# Power_Input.net
KiCad netlist of a schematic drawn in Altium Designer
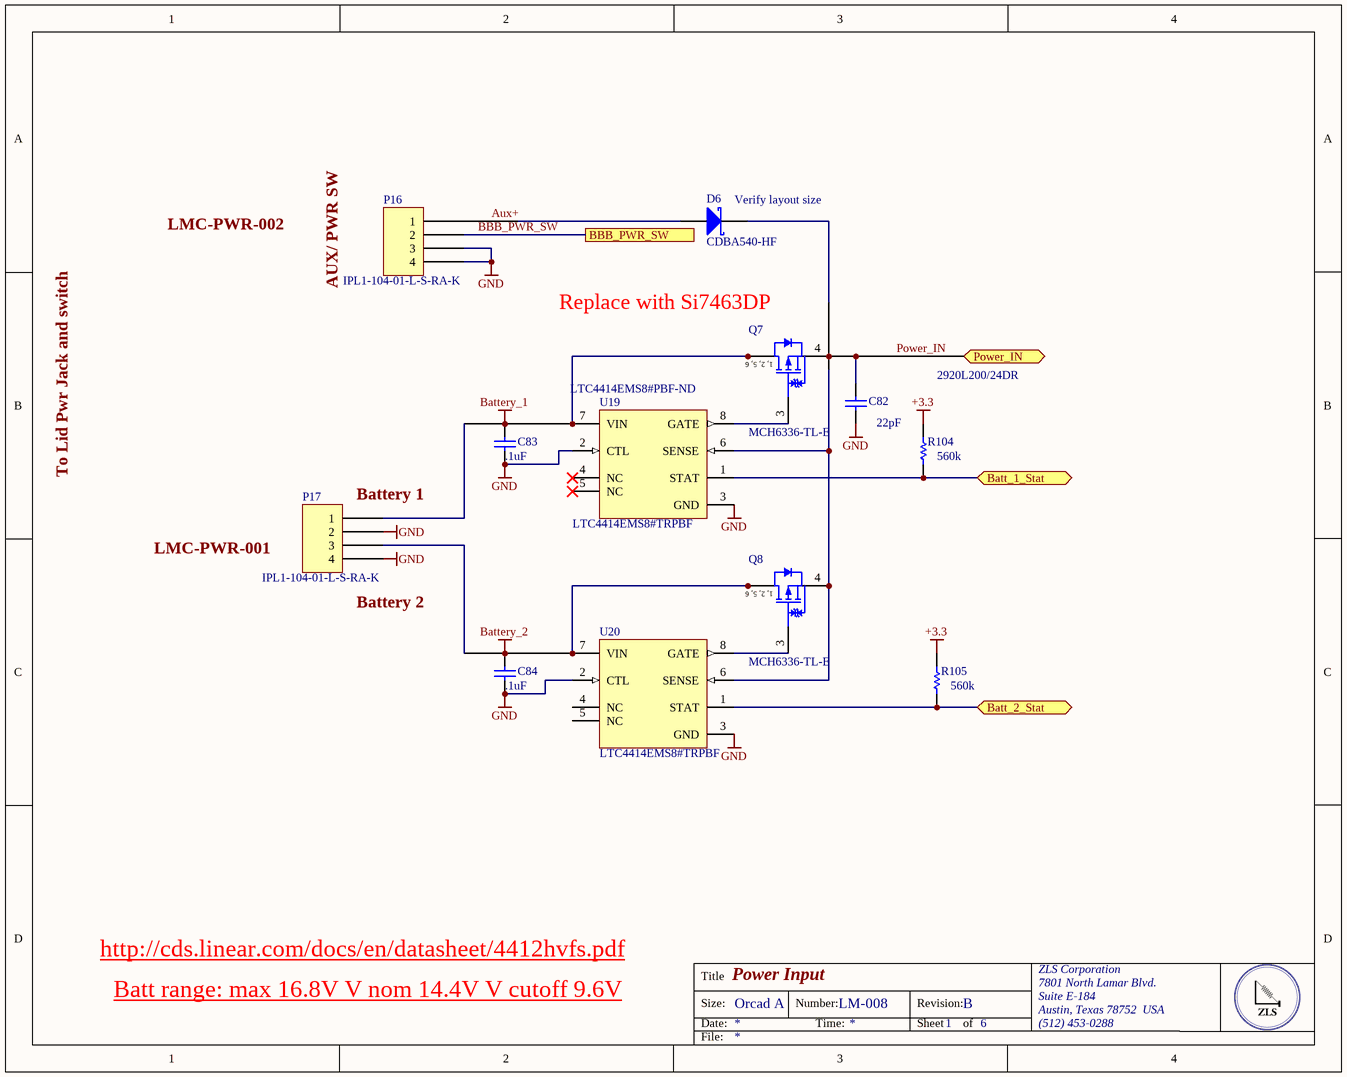
[diagram p0: Power_Input.SchDoc]

(export (version "E")
  (design (tool "Eeschema 10.0.6"))
  (components
    (comp (ref "C82")
      (value "CAP CER 10UF 6.3V X5R 1206")
      (footprint "CAPC1206(3216)130_N")
      (fields
        (field (name "MANUFACTURER") "Taiyo Yuden")
        (field (name "MANUFACTURER PART NUMBER") "JMK316BJ106ML-T")
        (field (name "TOLERANCE") "±20%")
        (field (name "CAPACITANCE") "22pF")
      )
      (libsource (lib "Altium Content Vault") (part "CMP-1037-04913-1"))
    )
    (comp (ref "C83")
      (value "CAP CER 10UF 6.3V X5R 1206")
      (footprint "CAPC1206(3216)130_N")
      (fields
        (field (name "MANUFACTURER") "Taiyo Yuden")
        (field (name "MANUFACTURER PART NUMBER") "JMK316BJ106ML-T")
        (field (name "TOLERANCE") "±20%")
        (field (name "CAPACITANCE") ".1uF")
      )
      (libsource (lib "Altium Content Vault") (part "CMP-1037-04913-1"))
    )
    (comp (ref "C84")
      (value "CAP CER 10UF 6.3V X5R 1206")
      (footprint "CAPC1206(3216)130_N")
      (fields
        (field (name "MANUFACTURER") "Taiyo Yuden")
        (field (name "MANUFACTURER PART NUMBER") "JMK316BJ106ML-T")
        (field (name "TOLERANCE") "±20%")
        (field (name "CAPACITANCE") ".1uF")
      )
      (libsource (lib "Altium Content Vault") (part "CMP-1037-04913-1"))
    )
    (comp (ref "D6")
      (value "CDBA540-HF")
      (footprint "VISH-DO-214AC-2_M")
      (description "DIODE SCHOTTKY 40V 5A DO214AB")
      (fields (field (name "MANUFACTURER") "Comchip Technology"))
      (libsource (lib "Miscellaneous Devices") (part "D Schottky"))
    )
    (comp (ref "P16")
      (value "IPL1-104-01-L-S-RA-K")
      (footprint "IPL1-104-01-L-S-RA-K")
      (fields
        (field (name "MANUFACTURER") "Samtec Inc.")
        (field (name "MANUFACTURER PART NUMBER") "IPL1-104-01-L-S-RA-K")
      )
      (libsource (lib "ZLS_Schematic_lib") (part "IPL1-104-01-L-S-RA-K"))
    )
    (comp (ref "P17")
      (value "IPL1-104-01-L-S-RA-K")
      (footprint "IPL1-104-01-L-S-RA-K")
      (fields
        (field (name "MANUFACTURER") "Samtec Inc.")
        (field (name "MANUFACTURER PART NUMBER") "IPL1-104-01-L-S-RA-K")
      )
      (libsource (lib "ZLS_Schematic_lib") (part "IPL1-104-01-L-S-RA-K"))
    )
    (comp (ref "Q7")
      (value "MCH6336-TL-E")
      (footprint "ONSC-MCPH-6_V")
      (description "P-Channel Power MOSFET, -12 V, -5 A, 43 mOhm, Single, 6-Pin MCPH, Pb-Free, Tape and Reel")
      (fields (field (name "MANUFACTURER") "ON Semiconductor"))
      (libsource (lib "Altium Content Vault") (part "CMP-1058-00598-1"))
    )
    (comp (ref "Q8")
      (value "MCH6336-TL-E")
      (footprint "ONSC-MCPH-6_V")
      (description "P-Channel Power MOSFET, -12 V, -5 A, 43 mOhm, Single, 6-Pin MCPH, Pb-Free, Tape and Reel")
      (fields (field (name "MANUFACTURER") "ON Semiconductor"))
      (libsource (lib "Altium Content Vault") (part "CMP-1058-00598-1"))
    )
    (comp (ref "R104")
      (value "560k")
      (footprint "RESC0402(1005)_L")
      (description "RES SMD 560K OHM 1% 1/10W 0402")
      (fields
        (field (name "MANUFACTURER") "Panasonic Electronic Components")
        (field (name "MANUFACTURER PART NUMBER") "ERJ-2RKF5603X")
      )
      (libsource (lib "Altium Content Vault") (part "CMP-1011-00927-1"))
    )
    (comp (ref "R105")
      (value "560k")
      (footprint "RESC0402(1005)_L")
      (description "RES SMD 560K OHM 1% 1/10W 0402")
      (fields
        (field (name "MANUFACTURER") "Panasonic Electronic Components")
        (field (name "MANUFACTURER PART NUMBER") "ERJ-2RKF5603X")
      )
      (libsource (lib "Altium Content Vault") (part "CMP-1011-00927-1"))
    )
    (comp (ref "U19")
      (value "LTC4414EMS8#TRPBF")
      (footprint "LT-MS8-8_L")
      (fields
        (field (name "SUPPLIER PART NUMBER 1") "LTC4414EMS8#PBF-ND")
        (field (name "MANUFACTURER") "Linear Technology/Analog Devices")
        (field (name "MANUFACTURER PART NUMBER") "LTC4414EMS8#PBF")
        (field (name "BASE PART NUMBER") "LTC4414")
      )
      (libsource (lib "Altium Content Vault") (part "CMP-0479-00214-1"))
    )
    (comp (ref "U20")
      (value "LTC4414EMS8#TRPBF")
      (footprint "LT-MS8-8_L")
      (fields
        (field (name "MANUFACTURER") "Linear Technology/Analog Devices")
        (field (name "MANUFACTURER PART NUMBER") "LTC4414EMS8#PBF")
        (field (name "BASE PART NUMBER") "LTC4414")
      )
      (libsource (lib "Altium Content Vault") (part "CMP-0479-00214-1"))
    )
  )
  (nets
    (net (code "1") (name "+3.3") (class "Default")
      (node (ref "R104") (pin "2") (pinfunction "2_2") (pintype "passive"))
      (node (ref "R105") (pin "2") (pinfunction "2_2") (pintype "passive"))
    )
    (net (code "2") (name "/Aux+") (class "Default")
      (node (ref "D6") (pin "1") (pinfunction "A_1") (pintype "passive"))
      (node (ref "P16") (pin "1") (pinfunction "1_1") (pintype "passive"))
    )
    (net (code "3") (name "/BBB_PWR_SW") (class "Default")
      (node (ref "P16") (pin "2") (pinfunction "2_2") (pintype "passive"))
    )
    (net (code "4") (name "/Batt_1_Stat") (class "Default")
      (node (ref "R104") (pin "1") (pinfunction "1_1") (pintype "passive"))
      (node (ref "U19") (pin "1") (pinfunction "STAT_1") (pintype "open_collector"))
    )
    (net (code "5") (name "/Batt_2_Stat") (class "Default")
      (node (ref "R105") (pin "1") (pinfunction "1_1") (pintype "passive"))
      (node (ref "U20") (pin "1") (pinfunction "STAT_1") (pintype "open_collector"))
    )
    (net (code "6") (name "/Power_IN") (class "Default")
      (node (ref "C82") (pin "2") (pinfunction "2_2") (pintype "passive"))
      (node (ref "D6") (pin "2") (pinfunction "K_2") (pintype "passive"))
      (node (ref "Q7") (pin "4") (pinfunction "S_4") (pintype "passive"))
      (node (ref "Q8") (pin "4") (pinfunction "S_4") (pintype "passive"))
      (node (ref "U19") (pin "6") (pinfunction "SENSE_6") (pintype "input"))
      (node (ref "U20") (pin "6") (pinfunction "SENSE_6") (pintype "input"))
    )
    (net (code "7") (name "Battery_1") (class "Default")
      (node (ref "C83") (pin "2") (pinfunction "2_2") (pintype "passive"))
      (node (ref "P17") (pin "1") (pinfunction "1_1") (pintype "passive"))
      (node (ref "Q7") (pin "1") (pinfunction "D_1") (pintype "passive"))
      (node (ref "Q7") (pin "2") (pinfunction "D_2") (pintype "passive"))
      (node (ref "Q7") (pin "5") (pinfunction "D_5") (pintype "passive"))
      (node (ref "Q7") (pin "6") (pinfunction "D_6") (pintype "passive"))
      (node (ref "U19") (pin "7") (pinfunction "VIN_7") (pintype "power_in"))
    )
    (net (code "8") (name "Battery_2") (class "Default")
      (node (ref "C84") (pin "2") (pinfunction "2_2") (pintype "passive"))
      (node (ref "P17") (pin "3") (pinfunction "3_3") (pintype "passive"))
      (node (ref "Q8") (pin "1") (pinfunction "D_1") (pintype "passive"))
      (node (ref "Q8") (pin "2") (pinfunction "D_2") (pintype "passive"))
      (node (ref "Q8") (pin "5") (pinfunction "D_5") (pintype "passive"))
      (node (ref "Q8") (pin "6") (pinfunction "D_6") (pintype "passive"))
      (node (ref "U20") (pin "7") (pinfunction "VIN_7") (pintype "power_in"))
    )
    (net (code "9") (name "GND") (class "Default")
      (node (ref "C82") (pin "1") (pinfunction "1_1") (pintype "passive"))
      (node (ref "C83") (pin "1") (pinfunction "1_1") (pintype "passive"))
      (node (ref "C84") (pin "1") (pinfunction "1_1") (pintype "passive"))
      (node (ref "P16") (pin "3") (pinfunction "3_3") (pintype "passive"))
      (node (ref "P16") (pin "4") (pinfunction "4_4") (pintype "passive"))
      (node (ref "P17") (pin "2") (pinfunction "2_2") (pintype "passive"))
      (node (ref "P17") (pin "4") (pinfunction "4_4") (pintype "passive"))
      (node (ref "U19") (pin "2") (pinfunction "CTL_2") (pintype "input"))
      (node (ref "U19") (pin "3") (pinfunction "GND_3") (pintype "power_in"))
      (node (ref "U20") (pin "2") (pinfunction "CTL_2") (pintype "input"))
      (node (ref "U20") (pin "3") (pinfunction "GND_3") (pintype "power_in"))
    )
    (net (code "10") (name "Net-(Q7-G)") (class "Default")
      (node (ref "Q7") (pin "3") (pinfunction "G_3") (pintype "passive"))
      (node (ref "U19") (pin "8") (pinfunction "GATE_8") (pintype "output"))
    )
    (net (code "11") (name "Net-(Q8-G)") (class "Default")
      (node (ref "Q8") (pin "3") (pinfunction "G_3") (pintype "passive"))
      (node (ref "U20") (pin "8") (pinfunction "GATE_8") (pintype "output"))
    )
    (net (code "12") (name "unconnected-(U19-NC-Pad4)") (class "Default")
      (node (ref "U19") (pin "4") (pinfunction "NC_4") (pintype "passive+no_connect"))
    )
    (net (code "13") (name "unconnected-(U19-NC-Pad5)") (class "Default")
      (node (ref "U19") (pin "5") (pinfunction "NC_5") (pintype "passive+no_connect"))
    )
    (net (code "14") (name "unconnected-(U20-NC-Pad4)") (class "Default")
      (node (ref "U20") (pin "4") (pinfunction "NC_4") (pintype "passive"))
    )
    (net (code "15") (name "unconnected-(U20-NC-Pad5)") (class "Default")
      (node (ref "U20") (pin "5") (pinfunction "NC_5") (pintype "passive"))
    )
  )
)
